# PowerSupply.net
KiCad netlist of a schematic drawn in Altium Designer
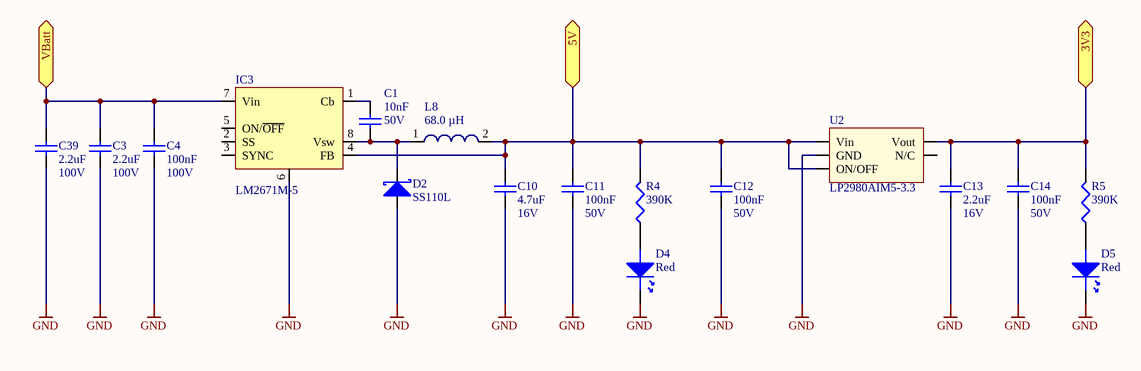
[diagram p0: PowerSupply.SchDoc]

(export (version "E")
  (design (tool "Eeschema 10.0.6"))
  (components
    (comp (ref "C1")
      (value "10nF")
      (footprint "C0603")
      (description "Capacitor, 10nF, 50V, X7R")
      (fields (field (name "VOLTAGE RATING") "50V"))
      (libsource (lib "AR_Capacitors_Ceramic") (part "10nF/0603/CER/50V"))
    )
    (comp (ref "C3")
      (value "2.2uF")
      (footprint "C-1210")
      (description "Capacitor, 2.2uF, 100V, X7R")
      (fields (field (name "VOLTAGE RATING") "100V"))
      (libsource (lib "AR_Capacitors_Ceramic") (part "2.2uF/1210/CER/100V"))
    )
    (comp (ref "C4")
      (value "100nF")
      (footprint "C-1206")
      (description "Capacitor, 100nF, 100V, X7R")
      (fields (field (name "VOLTAGE RATING") "100V"))
      (libsource (lib "AR_Capacitors_Ceramic") (part "100nF/1206/CER/100V"))
    )
    (comp (ref "C10")
      (value "4.7uF")
      (footprint "C-0805")
      (description "Capacitor, 4.7uF, 16V, X7R")
      (fields (field (name "VOLTAGE RATING") "16V"))
      (libsource (lib "AR_Capacitors_Ceramic") (part "4.7uF/0805/CER/16V"))
    )
    (comp (ref "C11")
      (value "100nF")
      (footprint "C-0805")
      (description "Capacitor, 100nF, 50V,  X7R")
      (fields (field (name "VOLTAGE RATING") "50V"))
      (libsource (lib "AR_Capacitors_Ceramic") (part "100nF/0805/CER/50V"))
    )
    (comp (ref "C12")
      (value "100nF")
      (footprint "C0603")
      (description "Capacitor, 100nF, 50V, X7R")
      (fields (field (name "VOLTAGE RATING") "50V"))
      (libsource (lib "AR_Capacitors_Ceramic") (part "100nF/0603/CER/50V"))
    )
    (comp (ref "C13")
      (value "2.2uF")
      (footprint "C0603")
      (description "Capacitor, 2.2uF, 16V, X5R")
      (fields (field (name "VOLTAGE RATING") "16V"))
      (libsource (lib "AR_Capacitors_Ceramic") (part "2.2uF/0603/CER/16V"))
    )
    (comp (ref "C14")
      (value "100nF")
      (footprint "C0603")
      (description "Capacitor, 100nF, 50V, X7R")
      (fields (field (name "VOLTAGE RATING") "50V"))
      (libsource (lib "AR_Capacitors_Ceramic") (part "100nF/0603/CER/50V"))
    )
    (comp (ref "C39")
      (value "2.2uF")
      (footprint "C-1210")
      (description "Capacitor, 2.2uF, 100V, X7R")
      (fields (field (name "VOLTAGE RATING") "100V"))
      (libsource (lib "AR_Capacitors_Ceramic") (part "2.2uF/1210/CER/100V"))
    )
    (comp (ref "D2")
      (value "SS110L")
      (footprint "SUB-SMA")
      (description "Diode Schottky, Vrrm: 100V, If: 1A, Vf: 0.9V")
      (libsource (lib "AR_Diodes") (part "SS110L"))
    )
    (comp (ref "D4")
      (value "Red")
      (footprint "D-0805")
      (description "Led, Red, Li:2.5mcd, Vf:1.8V, If:0.02A")
      (libsource (lib "AR_Misc") (part "SML-211UTT86K"))
    )
    (comp (ref "D5")
      (value "Red")
      (footprint "D-0805")
      (description "Led, Red, Li:2.5mcd, Vf:1.8V, If:0.02A")
      (libsource (lib "AR_Misc") (part "SML-211UTT86K"))
    )
    (comp (ref "IC3")
      (value "LM2671M-5")
      (footprint "SO-8")
      (description "5V DC/DC Converter")
      (libsource (lib "DannyLib") (part "LM2671M-5"))
    )
    (comp (ref "L8")
      (value "68.0 µH")
      (footprint "WE-LQ M")
      (description "SMD-RF-Inductor WE-LQ, L=68.0 µH")
      (fields (field (name "PARTNO") "744032680") (field (name "CREATED BY") "Christin Zierenner"))
      (libsource (lib "Altium_WE_eiSos_2-1_SMD_Power_Choke_100713") (part "WE-LQ M, 744032680"))
    )
    (comp (ref "R4")
      (value "390K")
      (footprint "0603")
      (description "Resistor, 390K, 1%, 0.1W, 75V, 50PPM, 0603")
      (libsource (lib "AR_Resistors_SMD") (part "390K/0603/0100W/75V"))
    )
    (comp (ref "R5")
      (value "390K")
      (footprint "0603")
      (description "Resistor, 390K, 1%, 0.1W, 75V, 50PPM, 0603")
      (libsource (lib "AR_Resistors_SMD") (part "390K/0603/0100W/75V"))
    )
    (comp (ref "U2")
      (value "LP2980AIM5-3.3")
      (footprint "TSOT23")
      (description "LDO, Out Voltage: 3.3V/50mA Ultra Low-Dropout Regulator")
      (libsource (lib "IC") (part "LP2980AIM5-3.3"))
    )
  )
  (nets
    (net (code "1") (name "/3V3") (class "Default")
      (node (ref "C13") (pin "2") (pinfunction "2_2") (pintype "passive"))
      (node (ref "C14") (pin "2") (pinfunction "2_2") (pintype "passive"))
      (node (ref "R5") (pin "2") (pinfunction "2_2") (pintype "passive"))
      (node (ref "U2") (pin "5") (pinfunction "Vout_5") (pintype "passive"))
    )
    (net (code "2") (name "/5V") (class "Default")
      (node (ref "C10") (pin "2") (pinfunction "2_2") (pintype "passive"))
      (node (ref "C11") (pin "2") (pinfunction "2_2") (pintype "passive"))
      (node (ref "C12") (pin "2") (pinfunction "2_2") (pintype "passive"))
      (node (ref "IC3") (pin "4") (pinfunction "FB_4") (pintype "power_in"))
      (node (ref "L8") (pin "2") (pinfunction "2_2") (pintype "passive"))
      (node (ref "R4") (pin "2") (pinfunction "2_2") (pintype "passive"))
      (node (ref "U2") (pin "1") (pinfunction "Vin_1") (pintype "passive"))
      (node (ref "U2") (pin "3") (pinfunction "ON/OFF_3") (pintype "passive"))
    )
    (net (code "3") (name "/VBatt") (class "Default")
      (node (ref "C3") (pin "2") (pinfunction "2_2") (pintype "passive"))
      (node (ref "C39") (pin "2") (pinfunction "2_2") (pintype "passive"))
      (node (ref "C4") (pin "2") (pinfunction "2_2") (pintype "passive"))
      (node (ref "IC3") (pin "7") (pinfunction "Vin_7") (pintype "power_in"))
    )
    (net (code "4") (name "GND") (class "Default")
      (node (ref "C10") (pin "1") (pinfunction "1_1") (pintype "passive"))
      (node (ref "C11") (pin "1") (pinfunction "1_1") (pintype "passive"))
      (node (ref "C12") (pin "1") (pinfunction "1_1") (pintype "passive"))
      (node (ref "C13") (pin "1") (pinfunction "1_1") (pintype "passive"))
      (node (ref "C14") (pin "1") (pinfunction "1_1") (pintype "passive"))
      (node (ref "C3") (pin "1") (pinfunction "1_1") (pintype "passive"))
      (node (ref "C39") (pin "1") (pinfunction "1_1") (pintype "passive"))
      (node (ref "C4") (pin "1") (pinfunction "1_1") (pintype "passive"))
      (node (ref "D2") (pin "1") (pinfunction "A_1") (pintype "passive"))
      (node (ref "D4") (pin "K") (pinfunction "K_K") (pintype "passive"))
      (node (ref "D5") (pin "K") (pinfunction "K_K") (pintype "passive"))
      (node (ref "IC3") (pin "6") (pinfunction "GND_6") (pintype "power_in"))
      (node (ref "U2") (pin "2") (pinfunction "GND_2") (pintype "passive"))
    )
    (net (code "5") (name "Net-(D2-K)") (class "Default")
      (node (ref "C1") (pin "1") (pinfunction "1_1") (pintype "passive"))
      (node (ref "D2") (pin "2") (pinfunction "K_2") (pintype "passive"))
      (node (ref "IC3") (pin "8") (pinfunction "Vsw_8") (pintype "power_in"))
      (node (ref "L8") (pin "1") (pinfunction "1_1") (pintype "passive"))
    )
    (net (code "6") (name "Net-(D4-PadA)") (class "Default")
      (node (ref "D4") (pin "A") (pinfunction "A_A") (pintype "passive"))
      (node (ref "R4") (pin "1") (pinfunction "1_1") (pintype "passive"))
    )
    (net (code "7") (name "Net-(D5-PadA)") (class "Default")
      (node (ref "D5") (pin "A") (pinfunction "A_A") (pintype "passive"))
      (node (ref "R5") (pin "1") (pinfunction "1_1") (pintype "passive"))
    )
    (net (code "8") (name "Net-(IC3-Cb)") (class "Default")
      (node (ref "C1") (pin "2") (pinfunction "2_2") (pintype "passive"))
      (node (ref "IC3") (pin "1") (pinfunction "Cb_1") (pintype "power_in"))
    )
    (net (code "9") (name "unconnected-(IC3-ON{slash}~{OFF}-Pad5)") (class "Default")
      (node (ref "IC3") (pin "5") (pinfunction "ON/~{OFF}_5") (pintype "power_in"))
    )
    (net (code "10") (name "unconnected-(IC3-SS-Pad2)") (class "Default")
      (node (ref "IC3") (pin "2") (pinfunction "SS_2") (pintype "power_in"))
    )
    (net (code "11") (name "unconnected-(IC3-SYNC-Pad3)") (class "Default")
      (node (ref "IC3") (pin "3") (pinfunction "SYNC_3") (pintype "power_in"))
    )
    (net (code "12") (name "unconnected-(U2-N{slash}C-Pad4)") (class "Default")
      (node (ref "U2") (pin "4") (pinfunction "N/C_4") (pintype "passive"))
    )
  )
)
